# breakout_MDBT40.net
KiCad netlist of a schematic drawn in EAGLE
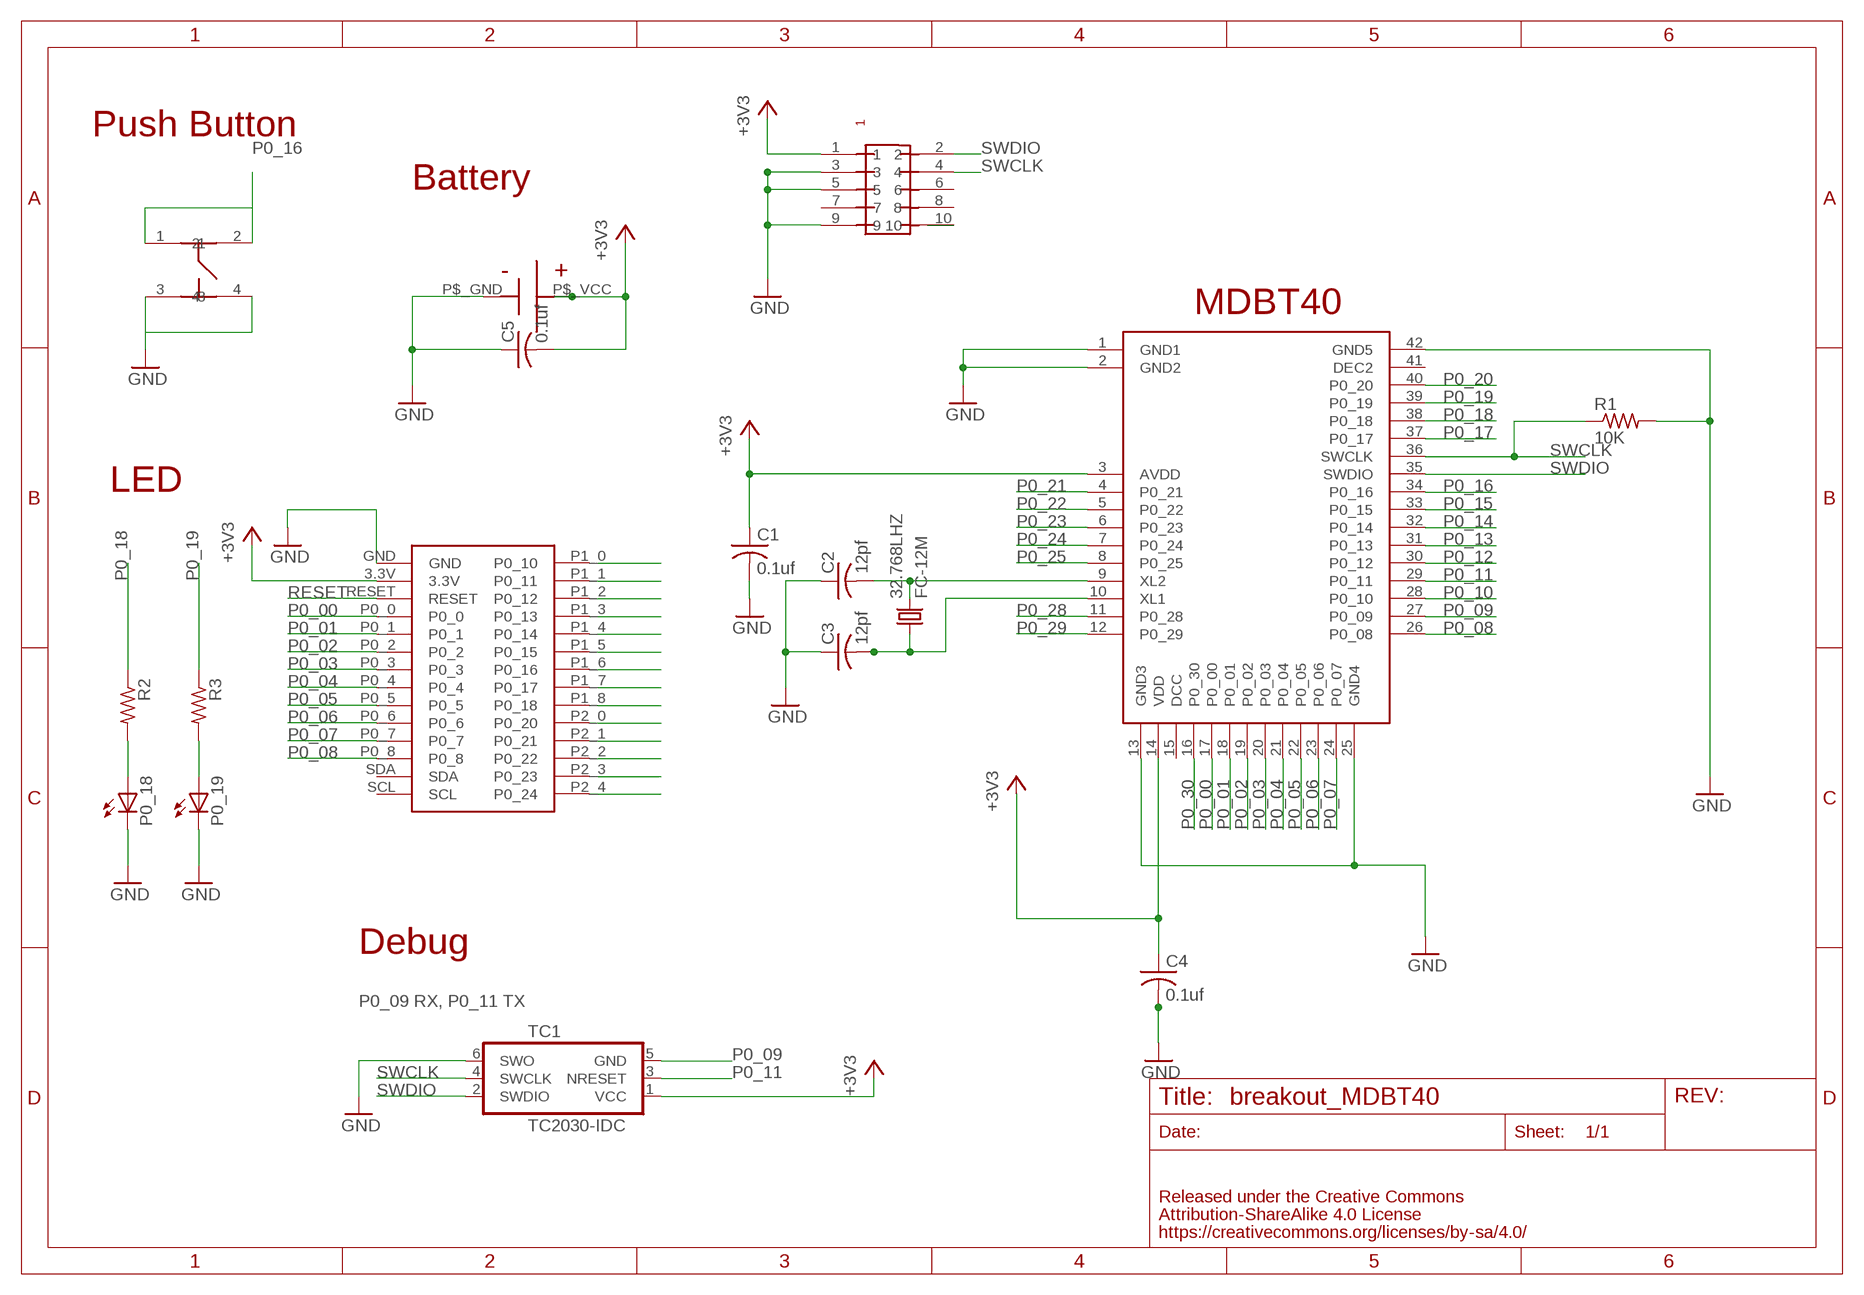
[diagram p0: schematic, sheet 1]

(export (version "E")
  (design (tool "Eeschema 10.0.6"))
  (components
    (comp (ref "32.768LHZ")
      (value "FC-12M")
      (footprint "eagle-import:FC-12M")
      (libsource (lib "eagle-import") (part "FC-12M"))
    )
    (comp (ref "C1")
      (value "0.1uf")
      (footprint "eagle-import:C0603")
      (libsource (lib "eagle-import") (part "C-USC0603"))
    )
    (comp (ref "C2")
      (value "12pf")
      (footprint "eagle-import:C0603")
      (libsource (lib "eagle-import") (part "C-USC0603"))
    )
    (comp (ref "C3")
      (value "12pf")
      (footprint "eagle-import:C0603")
      (libsource (lib "eagle-import") (part "C-USC0603"))
    )
    (comp (ref "C4")
      (value "0.1uf")
      (footprint "eagle-import:C0603")
      (libsource (lib "eagle-import") (part "C-USC0603"))
    )
    (comp (ref "C5")
      (value "0.1uf")
      (footprint "eagle-import:C0603")
      (libsource (lib "eagle-import") (part "C-USC0603"))
    )
    (comp (ref "P0_18")
      (value "LEDCHIP-LED0603")
      (footprint "eagle-import:CHIP-LED0603")
      (libsource (lib "eagle-import") (part "LEDCHIP-LED0603"))
    )
    (comp (ref "P0_19")
      (value "LEDCHIP-LED0603")
      (footprint "eagle-import:CHIP-LED0603")
      (libsource (lib "eagle-import") (part "LEDCHIP-LED0603"))
    )
    (comp (ref "R1")
      (value "10K")
      (footprint "eagle-import:R0603")
      (libsource (lib "eagle-import") (part "R-US_R0603"))
    )
    (comp (ref "R2")
      (value "R-US_R0603")
      (footprint "eagle-import:R0603")
      (libsource (lib "eagle-import") (part "R-US_R0603"))
    )
    (comp (ref "R3")
      (value "R-US_R0603")
      (footprint "eagle-import:R0603")
      (libsource (lib "eagle-import") (part "R-US_R0603"))
    )
    (comp (ref "TC1")
      (value "TC2030-IDC")
      (footprint "eagle-import:TC2030-IDC")
      (libsource (lib "eagle-import") (part "TC2030-IDC"))
    )
    (comp (ref "U$1")
      (value "RAYTAC-MDBT40")
      (footprint "eagle-import:RAYTAC-MDBT40")
      (libsource (lib "eagle-import") (part "RAYTAC-MDBT40"))
    )
    (comp (ref "U$2")
      (value "SMTU2450-TOP")
      (footprint "eagle-import:SMTU2450")
      (libsource (lib "eagle-import") (part "SMTU2450-TOP"))
    )
    (comp (ref "U$3")
      (value "BREAKOUT_BLE_NORDIC")
      (footprint "eagle-import:BREAKOUT_BLE_NORDIC")
      (libsource (lib "eagle-import") (part "BREAKOUT_BLE_NORDIC"))
    )
    (comp (ref "U$4")
      (value "PIN-HEADER-SMT(1.27MM)2X5")
      (footprint "eagle-import:PIN-HEADER-SMT(1.27MM)2X5")
      (libsource (lib "eagle-import") (part "PIN-HEADER-SMT(1.27MM)2X5"))
    )
    (comp (ref "U$5")
      (value "SWICTH-4P(KMR2)")
      (footprint "eagle-import:SWITCH-4P(KMR2)")
      (libsource (lib "eagle-import") (part "SWICTH-4P(KMR2)"))
    )
  )
  (nets
    (net (code "1") (name "+3V3") (class "Default")
      (node (ref "C1") (pin "1") (pinfunction "1_1") (pintype "passive"))
      (node (ref "C4") (pin "1") (pinfunction "1_1") (pintype "passive"))
      (node (ref "C5") (pin "2") (pinfunction "2_2") (pintype "passive"))
      (node (ref "TC1") (pin "1") (pinfunction "VCC_1") (pintype "passive"))
      (node (ref "U$1") (pin "14") (pinfunction "VDD_14") (pintype "bidirectional"))
      (node (ref "U$1") (pin "3") (pinfunction "AVDD_3") (pintype "bidirectional"))
      (node (ref "U$2") (pin "P$_VCC") (pinfunction "+_P$_VCC") (pintype "bidirectional"))
      (node (ref "U$3") (pin "3.3V") (pinfunction "3.3V_3.3V") (pintype "bidirectional"))
      (node (ref "U$4") (pin "1") (pinfunction "1_1") (pintype "bidirectional"))
    )
    (net (code "2") (name "/P0_00") (class "Default")
      (node (ref "U$1") (pin "17") (pinfunction "P0_00_17") (pintype "bidirectional"))
      (node (ref "U$3") (pin "P0_0") (pinfunction "P0_0_P0_0") (pintype "bidirectional"))
    )
    (net (code "3") (name "/P0_01") (class "Default")
      (node (ref "U$1") (pin "18") (pinfunction "P0_01_18") (pintype "bidirectional"))
      (node (ref "U$3") (pin "P0_1") (pinfunction "P0_1_P0_1") (pintype "bidirectional"))
    )
    (net (code "4") (name "/P0_02") (class "Default")
      (node (ref "U$1") (pin "19") (pinfunction "P0_02_19") (pintype "bidirectional"))
      (node (ref "U$3") (pin "P0_2") (pinfunction "P0_2_P0_2") (pintype "bidirectional"))
    )
    (net (code "5") (name "/P0_03") (class "Default")
      (node (ref "U$1") (pin "20") (pinfunction "P0_03_20") (pintype "bidirectional"))
      (node (ref "U$3") (pin "P0_3") (pinfunction "P0_3_P0_3") (pintype "bidirectional"))
    )
    (net (code "6") (name "/P0_04") (class "Default")
      (node (ref "U$1") (pin "21") (pinfunction "P0_04_21") (pintype "bidirectional"))
      (node (ref "U$3") (pin "P0_4") (pinfunction "P0_4_P0_4") (pintype "bidirectional"))
    )
    (net (code "7") (name "/P0_05") (class "Default")
      (node (ref "U$1") (pin "22") (pinfunction "P0_05_22") (pintype "bidirectional"))
      (node (ref "U$3") (pin "P0_5") (pinfunction "P0_5_P0_5") (pintype "bidirectional"))
    )
    (net (code "8") (name "/P0_06") (class "Default")
      (node (ref "U$1") (pin "23") (pinfunction "P0_06_23") (pintype "bidirectional"))
      (node (ref "U$3") (pin "P0_6") (pinfunction "P0_6_P0_6") (pintype "bidirectional"))
    )
    (net (code "9") (name "/P0_07") (class "Default")
      (node (ref "U$1") (pin "24") (pinfunction "P0_07_24") (pintype "bidirectional"))
      (node (ref "U$3") (pin "P0_7") (pinfunction "P0_7_P0_7") (pintype "bidirectional"))
    )
    (net (code "10") (name "/P0_08") (class "Default")
      (node (ref "U$1") (pin "26") (pinfunction "P0_08_26") (pintype "bidirectional"))
      (node (ref "U$3") (pin "P0_8") (pinfunction "P0_8_P0_8") (pintype "bidirectional"))
    )
    (net (code "11") (name "/P0_09") (class "Default")
      (node (ref "TC1") (pin "5") (pinfunction "GND_5") (pintype "passive"))
      (node (ref "U$1") (pin "27") (pinfunction "P0_09_27") (pintype "bidirectional"))
    )
    (net (code "12") (name "/P0_10") (class "Default")
      (node (ref "U$1") (pin "28") (pinfunction "P0_10_28") (pintype "bidirectional"))
      (node (ref "U$3") (pin "P1_0") (pinfunction "P0_10_P1_0") (pintype "bidirectional"))
    )
    (net (code "13") (name "/P0_11") (class "Default")
      (node (ref "TC1") (pin "3") (pinfunction "NRESET_3") (pintype "passive"))
      (node (ref "U$1") (pin "29") (pinfunction "P0_11_29") (pintype "bidirectional"))
      (node (ref "U$3") (pin "P1_1") (pinfunction "P0_11_P1_1") (pintype "bidirectional"))
    )
    (net (code "14") (name "/P0_12") (class "Default")
      (node (ref "U$1") (pin "30") (pinfunction "P0_12_30") (pintype "bidirectional"))
      (node (ref "U$3") (pin "P1_2") (pinfunction "P0_12_P1_2") (pintype "bidirectional"))
    )
    (net (code "15") (name "/P0_13") (class "Default")
      (node (ref "U$1") (pin "31") (pinfunction "P0_13_31") (pintype "bidirectional"))
      (node (ref "U$3") (pin "P1_3") (pinfunction "P0_13_P1_3") (pintype "bidirectional"))
    )
    (net (code "16") (name "/P0_14") (class "Default")
      (node (ref "U$1") (pin "32") (pinfunction "P0_14_32") (pintype "bidirectional"))
      (node (ref "U$3") (pin "P1_4") (pinfunction "P0_14_P1_4") (pintype "bidirectional"))
    )
    (net (code "17") (name "/P0_15") (class "Default")
      (node (ref "U$1") (pin "33") (pinfunction "P0_15_33") (pintype "bidirectional"))
      (node (ref "U$3") (pin "P1_5") (pinfunction "P0_15_P1_5") (pintype "bidirectional"))
    )
    (net (code "18") (name "/P0_16") (class "Default")
      (node (ref "U$1") (pin "34") (pinfunction "P0_16_34") (pintype "bidirectional"))
      (node (ref "U$3") (pin "P1_6") (pinfunction "P0_16_P1_6") (pintype "bidirectional"))
      (node (ref "U$5") (pin "1") (pinfunction "1_1") (pintype "bidirectional"))
      (node (ref "U$5") (pin "2") (pinfunction "2_2") (pintype "bidirectional"))
    )
    (net (code "19") (name "/P0_17") (class "Default")
      (node (ref "U$1") (pin "37") (pinfunction "P0_17_37") (pintype "bidirectional"))
      (node (ref "U$3") (pin "P1_7") (pinfunction "P0_17_P1_7") (pintype "bidirectional"))
    )
    (net (code "20") (name "/P0_18") (class "Default")
      (node (ref "R2") (pin "1") (pinfunction "1_1") (pintype "passive"))
      (node (ref "U$1") (pin "38") (pinfunction "P0_18_38") (pintype "bidirectional"))
      (node (ref "U$3") (pin "P1_8") (pinfunction "P0_18_P1_8") (pintype "bidirectional"))
    )
    (net (code "21") (name "/P0_19") (class "Default")
      (node (ref "R3") (pin "1") (pinfunction "1_1") (pintype "passive"))
      (node (ref "U$1") (pin "39") (pinfunction "P0_19_39") (pintype "bidirectional"))
    )
    (net (code "22") (name "/P0_20") (class "Default")
      (node (ref "U$1") (pin "40") (pinfunction "P0_20_40") (pintype "bidirectional"))
      (node (ref "U$3") (pin "P2_0") (pinfunction "P0_20_P2_0") (pintype "bidirectional"))
    )
    (net (code "23") (name "/P0_21") (class "Default")
      (node (ref "U$1") (pin "4") (pinfunction "P0_21_4") (pintype "bidirectional"))
      (node (ref "U$3") (pin "P2_1") (pinfunction "P0_21_P2_1") (pintype "bidirectional"))
    )
    (net (code "24") (name "/P0_22") (class "Default")
      (node (ref "U$1") (pin "5") (pinfunction "P0_22_5") (pintype "bidirectional"))
      (node (ref "U$3") (pin "P2_2") (pinfunction "P0_22_P2_2") (pintype "bidirectional"))
    )
    (net (code "25") (name "/P0_23") (class "Default")
      (node (ref "U$1") (pin "6") (pinfunction "P0_23_6") (pintype "bidirectional"))
      (node (ref "U$3") (pin "P2_3") (pinfunction "P0_23_P2_3") (pintype "bidirectional"))
    )
    (net (code "26") (name "/P0_24") (class "Default")
      (node (ref "U$1") (pin "7") (pinfunction "P0_24_7") (pintype "bidirectional"))
      (node (ref "U$3") (pin "P2_4") (pinfunction "P0_24_P2_4") (pintype "bidirectional"))
    )
    (net (code "27") (name "/P0_25") (class "Default")
      (node (ref "U$1") (pin "8") (pinfunction "P0_25_8") (pintype "bidirectional"))
    )
    (net (code "28") (name "/P0_28") (class "Default")
      (node (ref "U$1") (pin "11") (pinfunction "P0_28_11") (pintype "bidirectional"))
    )
    (net (code "29") (name "/P0_29") (class "Default")
      (node (ref "U$1") (pin "12") (pinfunction "P0_29_12") (pintype "bidirectional"))
    )
    (net (code "30") (name "/P0_30") (class "Default")
      (node (ref "U$1") (pin "16") (pinfunction "P0_30_16") (pintype "bidirectional"))
    )
    (net (code "31") (name "/RESET") (class "Default")
      (node (ref "U$3") (pin "RESET") (pinfunction "RESET_RESET") (pintype "bidirectional"))
    )
    (net (code "32") (name "/SWCLK") (class "Default")
      (node (ref "R1") (pin "1") (pinfunction "1_1") (pintype "passive"))
      (node (ref "TC1") (pin "4") (pinfunction "SWCLK_4") (pintype "passive"))
      (node (ref "U$1") (pin "36") (pinfunction "SWCLK_36") (pintype "bidirectional"))
      (node (ref "U$4") (pin "4") (pinfunction "4_4") (pintype "bidirectional"))
    )
    (net (code "33") (name "/SWDIO") (class "Default")
      (node (ref "TC1") (pin "2") (pinfunction "SWDIO_2") (pintype "passive"))
      (node (ref "U$1") (pin "35") (pinfunction "SWDIO_35") (pintype "bidirectional"))
      (node (ref "U$4") (pin "2") (pinfunction "2_2") (pintype "bidirectional"))
    )
    (net (code "34") (name "GND") (class "Default")
      (node (ref "C1") (pin "2") (pinfunction "2_2") (pintype "passive"))
      (node (ref "C2") (pin "1") (pinfunction "1_1") (pintype "passive"))
      (node (ref "C3") (pin "1") (pinfunction "1_1") (pintype "passive"))
      (node (ref "C4") (pin "2") (pinfunction "2_2") (pintype "passive"))
      (node (ref "C5") (pin "1") (pinfunction "1_1") (pintype "passive"))
      (node (ref "P0_18") (pin "C") (pinfunction "C_C") (pintype "passive"))
      (node (ref "P0_19") (pin "C") (pinfunction "C_C") (pintype "passive"))
      (node (ref "R1") (pin "2") (pinfunction "2_2") (pintype "passive"))
      (node (ref "TC1") (pin "6") (pinfunction "SWO_6") (pintype "passive"))
      (node (ref "U$1") (pin "1") (pinfunction "GND1_1") (pintype "bidirectional"))
      (node (ref "U$1") (pin "13") (pinfunction "GND3_13") (pintype "bidirectional"))
      (node (ref "U$1") (pin "2") (pinfunction "GND2_2") (pintype "bidirectional"))
      (node (ref "U$1") (pin "25") (pinfunction "GND4_25") (pintype "bidirectional"))
      (node (ref "U$1") (pin "42") (pinfunction "GND5_42") (pintype "bidirectional"))
      (node (ref "U$2") (pin "P$_GND") (pinfunction "-_P$_GND") (pintype "bidirectional"))
      (node (ref "U$3") (pin "GND") (pinfunction "GND_GND") (pintype "bidirectional"))
      (node (ref "U$4") (pin "3") (pinfunction "3_3") (pintype "bidirectional"))
      (node (ref "U$4") (pin "5") (pinfunction "5_5") (pintype "bidirectional"))
      (node (ref "U$4") (pin "9") (pinfunction "9_9") (pintype "bidirectional"))
      (node (ref "U$5") (pin "3") (pinfunction "3_3") (pintype "bidirectional"))
      (node (ref "U$5") (pin "4") (pinfunction "4_4") (pintype "bidirectional"))
    )
    (net (code "35") (name "Net-(P0_18-PadA)") (class "Default")
      (node (ref "P0_18") (pin "A") (pinfunction "A_A") (pintype "passive"))
      (node (ref "R2") (pin "2") (pinfunction "2_2") (pintype "passive"))
    )
    (net (code "36") (name "Net-(P0_19-PadA)") (class "Default")
      (node (ref "P0_19") (pin "A") (pinfunction "A_A") (pintype "passive"))
      (node (ref "R3") (pin "2") (pinfunction "2_2") (pintype "passive"))
    )
    (net (code "37") (name "Net-(U$1-XL1)") (class "Default")
      (node (ref "32.768LHZ") (pin "1") (pinfunction "1_1") (pintype "passive"))
      (node (ref "C3") (pin "2") (pinfunction "2_2") (pintype "passive"))
      (node (ref "U$1") (pin "10") (pinfunction "XL1_10") (pintype "bidirectional"))
    )
    (net (code "38") (name "Net-(U$1-XL2)") (class "Default")
      (node (ref "32.768LHZ") (pin "2") (pinfunction "2_2") (pintype "passive"))
      (node (ref "C2") (pin "2") (pinfunction "2_2") (pintype "passive"))
      (node (ref "U$1") (pin "9") (pinfunction "XL2_9") (pintype "bidirectional"))
    )
    (net (code "39") (name "unconnected-(U$1-DCC-Pad15)") (class "Default")
      (node (ref "U$1") (pin "15") (pinfunction "DCC_15") (pintype "bidirectional"))
    )
    (net (code "40") (name "unconnected-(U$1-DEC2-Pad41)") (class "Default")
      (node (ref "U$1") (pin "41") (pinfunction "DEC2_41") (pintype "bidirectional"))
    )
    (net (code "41") (name "unconnected-(U$3-PadSCL)") (class "Default")
      (node (ref "U$3") (pin "SCL") (pinfunction "SCL_SCL") (pintype "bidirectional"))
    )
    (net (code "42") (name "unconnected-(U$3-PadSDA)") (class "Default")
      (node (ref "U$3") (pin "SDA") (pinfunction "SDA_SDA") (pintype "bidirectional"))
    )
    (net (code "43") (name "unconnected-(U$4-Pad6)") (class "Default")
      (node (ref "U$4") (pin "6") (pinfunction "6_6") (pintype "bidirectional"))
    )
    (net (code "44") (name "unconnected-(U$4-Pad7)") (class "Default")
      (node (ref "U$4") (pin "7") (pinfunction "7_7") (pintype "bidirectional"))
    )
    (net (code "45") (name "unconnected-(U$4-Pad8)") (class "Default")
      (node (ref "U$4") (pin "8") (pinfunction "8_8") (pintype "bidirectional"))
    )
    (net (code "46") (name "unconnected-(U$4-Pad10)") (class "Default")
      (node (ref "U$4") (pin "10") (pinfunction "10_10") (pintype "bidirectional"))
    )
  )
)
